# CommsTransceiverSupply.net
KiCad netlist of a schematic drawn in EAGLE
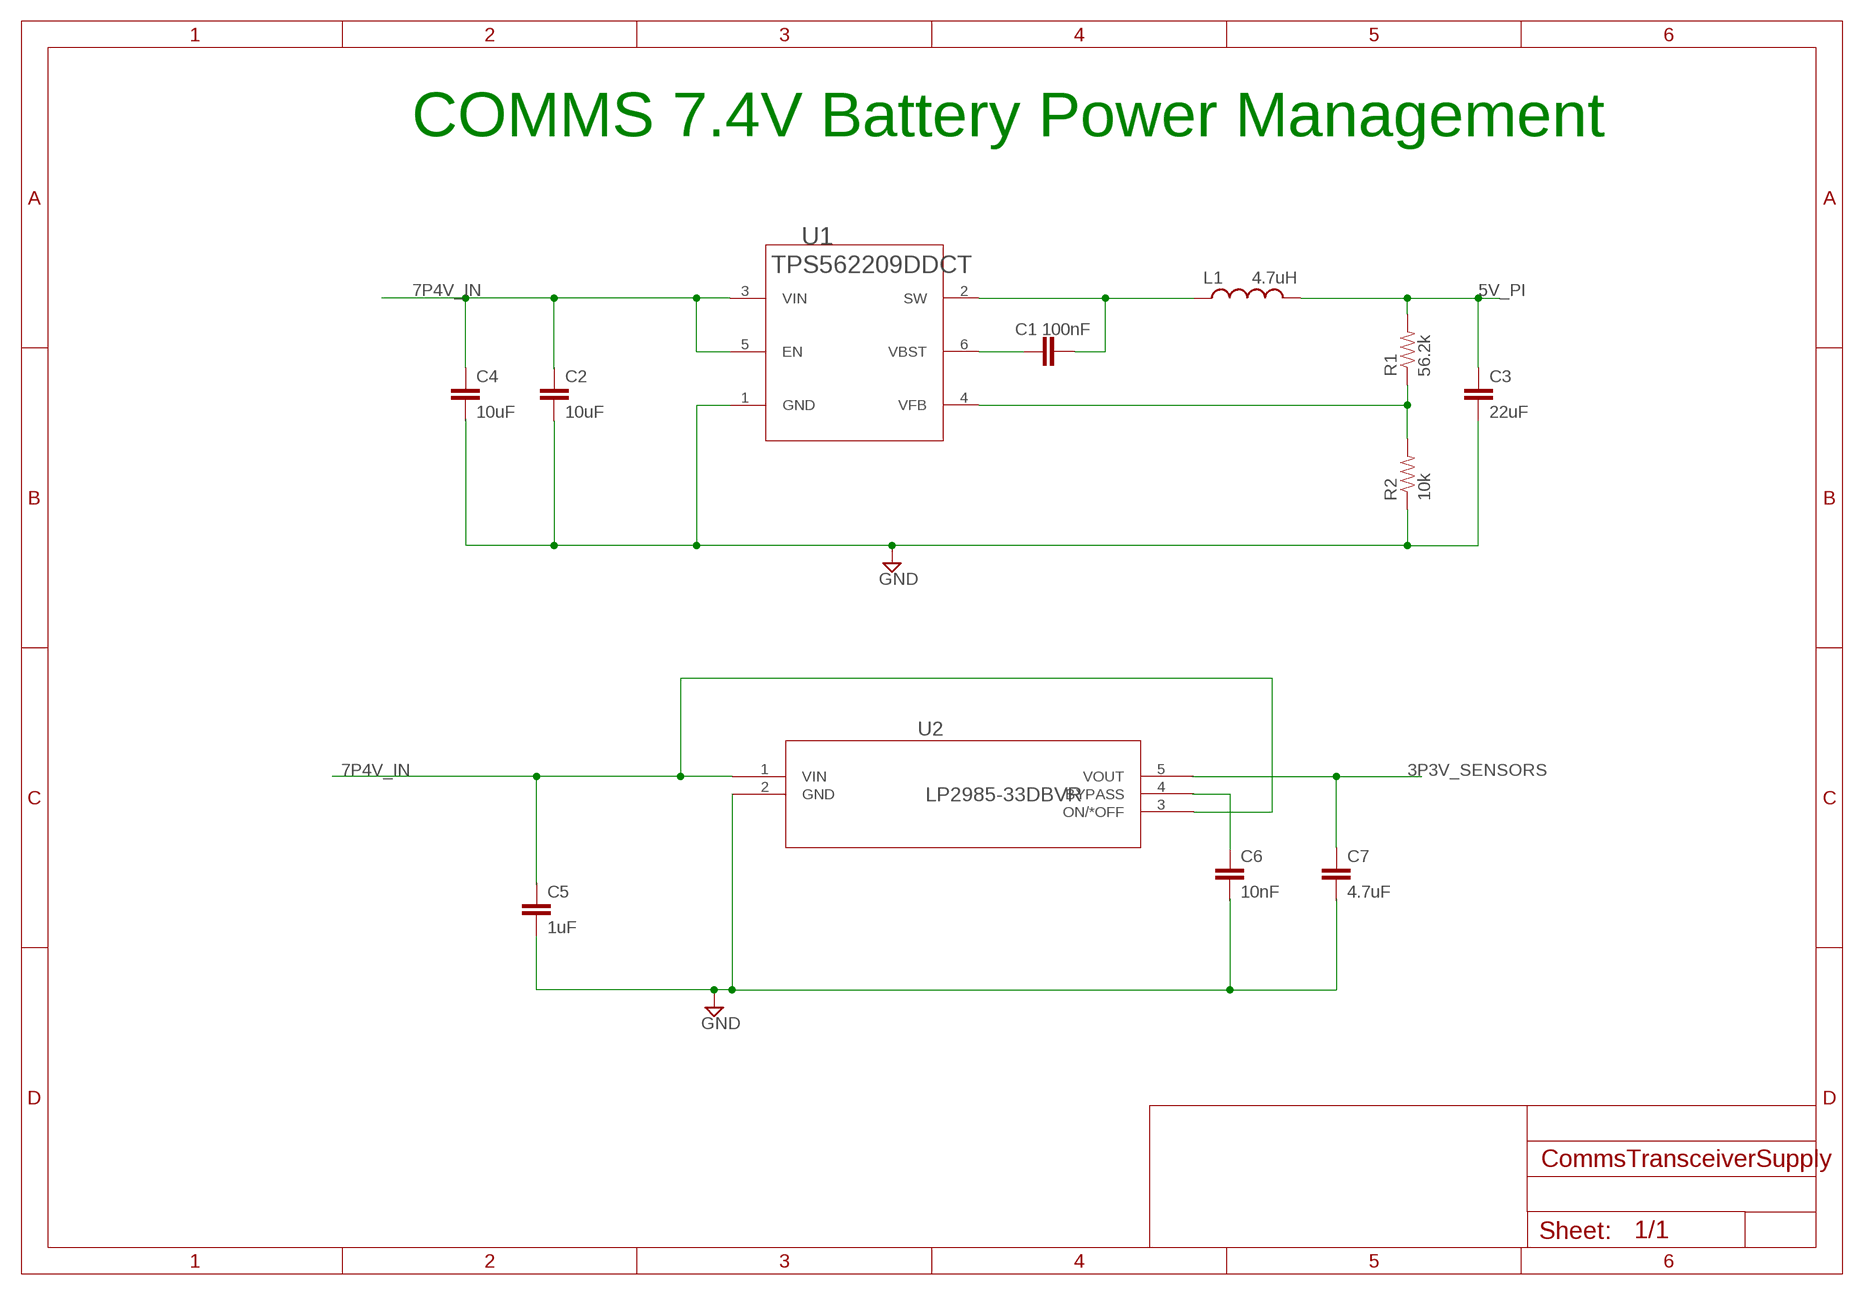
[diagram p0: schematic, sheet 1]

(export (version "E")
  (design (tool "Eeschema 10.0.6"))
  (components
    (comp (ref "C1")
      (value "100nF")
      (footprint "eagle-import:C0805")
      (fields
        (field (name "MANUFACTURER") "AVX Corporation")
        (field (name "TOLERANCE") "10%")
        (field (name "VOLTAGE") "25V")
      )
      (libsource (lib "eagle-import") (part "CAP_0805_100NF0"))
    )
    (comp (ref "C2")
      (value "10uF")
      (footprint "eagle-import:C0805")
      (fields
        (field (name "MANUFACTURER") "Murata Electronics North America")
        (field (name "TOLERANCE") "10%")
        (field (name "VOLTAGE") "16V")
      )
      (libsource (lib "eagle-import") (part "CAP_0805_10UF0"))
    )
    (comp (ref "C3")
      (value "22uF")
      (footprint "eagle-import:C1206")
      (fields
        (field (name "MANUFACTURER") "Murata Electronics North America")
        (field (name "TOLERANCE") "20%")
        (field (name "VOLTAGE") "10V")
      )
      (libsource (lib "eagle-import") (part "CAP_1206_22UF0"))
    )
    (comp (ref "C4")
      (value "10uF")
      (footprint "eagle-import:C0805")
      (fields
        (field (name "MANUFACTURER") "Murata Electronics North America")
        (field (name "TOLERANCE") "10%")
        (field (name "VOLTAGE") "16V")
      )
      (libsource (lib "eagle-import") (part "CAP_0805_10UF0"))
    )
    (comp (ref "C5")
      (value "1uF")
      (footprint "eagle-import:C0603")
      (fields
        (field (name "MANUFACTURER") "Murata")
        (field (name "TOLERANCE") "10%")
        (field (name "VOLTAGE") "16V")
      )
      (libsource (lib "eagle-import") (part "CAP_0603_1UF0"))
    )
    (comp (ref "C6")
      (value "10nF")
      (footprint "eagle-import:C0805")
      (fields
        (field (name "MANUFACTURER") "Kemet")
        (field (name "TOLERANCE") "10%")
        (field (name "VOLTAGE") "50V")
      )
      (libsource (lib "eagle-import") (part "CAP_0805_10NF0"))
    )
    (comp (ref "C7")
      (value "4.7uF")
      (footprint "eagle-import:C0603")
      (fields
        (field (name "MANUFACTURER") "Murata")
        (field (name "TOLERANCE") "10%")
        (field (name "VOLTAGE") "6.3V")
      )
      (libsource (lib "eagle-import") (part "CAP_0603_4UH7"))
    )
    (comp (ref "L1")
      (value "4.7uH")
      (footprint "eagle-import:SRN6045-4R7Y")
      (fields (field (name "MANUFACTURER") "Bourns Inc.") (field (name "TOLERANCE") "30%"))
      (libsource (lib "eagle-import") (part "L_4UH7"))
    )
    (comp (ref "R1")
      (value "56.2k")
      (footprint "eagle-import:R0603")
      (fields
        (field (name "MANUFACTURER") "Panasonic")
        (field (name "POWER") "1/10W")
        (field (name "TOLERANCE") "1%")
      )
      (libsource (lib "eagle-import") (part "RES_0603_56R2"))
    )
    (comp (ref "R2")
      (value "10k")
      (footprint "eagle-import:R0603")
      (fields
        (field (name "MANUFACTURER") "Panasonic")
        (field (name "POWER") "1/10W")
        (field (name "TOLERANCE") "1%")
      )
      (libsource (lib "eagle-import") (part "RES_0603_10R0"))
    )
    (comp (ref "U1")
      (value "TPS562209DDCT")
      (footprint "eagle-import:DDC0006A")
      (fields (field (name "MANUFACTURER") "Texas Instruments"))
      (libsource (lib "eagle-import") (part "TPS562209DDCR"))
    )
    (comp (ref "U2")
      (value "LP2985-33DBVR")
      (footprint "eagle-import:DBV5")
      (fields (field (name "MANUFACTURER") "Texas Instruments"))
      (libsource (lib "eagle-import") (part "LP2985-33_DBV_5"))
    )
  )
  (nets
    (net (code "1") (name "/3P3V_SENSORS") (class "Default")
      (node (ref "C7") (pin "1") (pinfunction "1_1") (pintype "passive"))
      (node (ref "U2") (pin "5") (pinfunction "VOUT_5") (pintype "output"))
    )
    (net (code "2") (name "/5V_PI") (class "Default")
      (node (ref "C3") (pin "1") (pinfunction "1_1") (pintype "passive"))
      (node (ref "L1") (pin "2") (pinfunction "2_2") (pintype "passive"))
      (node (ref "R1") (pin "2") (pinfunction "2_2") (pintype "passive"))
    )
    (net (code "3") (name "/7P4V_IN") (class "Default")
      (node (ref "C2") (pin "1") (pinfunction "1_1") (pintype "passive"))
      (node (ref "C4") (pin "1") (pinfunction "1_1") (pintype "passive"))
      (node (ref "C5") (pin "1") (pinfunction "1_1") (pintype "passive"))
      (node (ref "U1") (pin "3") (pinfunction "VIN_3") (pintype "power_in"))
      (node (ref "U1") (pin "5") (pinfunction "EN_5") (pintype "input"))
      (node (ref "U2") (pin "1") (pinfunction "VIN_1") (pintype "input"))
      (node (ref "U2") (pin "3") (pinfunction "ON/*OFF_3") (pintype "passive"))
    )
    (net (code "4") (name "GND") (class "Default")
      (node (ref "C2") (pin "2") (pinfunction "2_2") (pintype "passive"))
      (node (ref "C3") (pin "2") (pinfunction "2_2") (pintype "passive"))
      (node (ref "C4") (pin "2") (pinfunction "2_2") (pintype "passive"))
      (node (ref "C5") (pin "2") (pinfunction "2_2") (pintype "passive"))
      (node (ref "C6") (pin "2") (pinfunction "2_2") (pintype "passive"))
      (node (ref "C7") (pin "2") (pinfunction "2_2") (pintype "passive"))
      (node (ref "R2") (pin "1") (pinfunction "1_1") (pintype "passive"))
      (node (ref "U1") (pin "1") (pinfunction "GND_1") (pintype "power_in"))
      (node (ref "U2") (pin "2") (pinfunction "GND_2") (pintype "power_in"))
    )
    (net (code "5") (name "Net-(U1-SW)") (class "Default")
      (node (ref "C1") (pin "2") (pinfunction "2_2") (pintype "passive"))
      (node (ref "L1") (pin "1") (pinfunction "1_1") (pintype "passive"))
      (node (ref "U1") (pin "2") (pinfunction "SW_2") (pintype "power_in"))
    )
    (net (code "6") (name "Net-(U1-VFB)") (class "Default")
      (node (ref "R1") (pin "1") (pinfunction "1_1") (pintype "passive"))
      (node (ref "R2") (pin "2") (pinfunction "2_2") (pintype "passive"))
      (node (ref "U1") (pin "4") (pinfunction "VFB_4") (pintype "input"))
    )
    (net (code "7") (name "Net-(U2-BYPASS)") (class "Default")
      (node (ref "C6") (pin "1") (pinfunction "1_1") (pintype "passive"))
      (node (ref "U2") (pin "4") (pinfunction "BYPASS_4") (pintype "passive"))
    )
    (net (code "8") (name "unconnected-(C1-Pad1)") (class "Default")
      (node (ref "C1") (pin "1") (pinfunction "1_1") (pintype "passive"))
    )
    (net (code "9") (name "unconnected-(U1-VBST-Pad6)") (class "Default")
      (node (ref "U1") (pin "6") (pinfunction "VBST_6") (pintype "power_in"))
    )
  )
)
